# psu_temp.net
KiCad netlist of a schematic drawn in Altium Designer
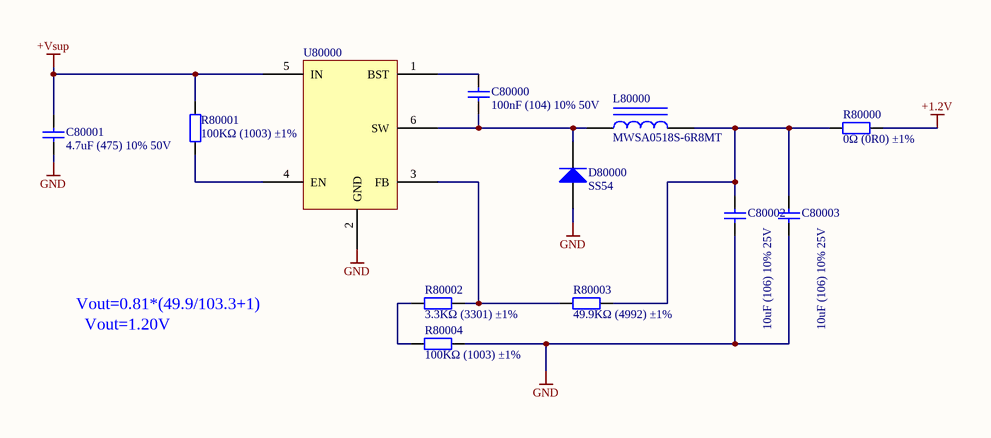
[diagram p0: psu_temp.SchDoc]

(export (version "E")
  (design (tool "Eeschema 10.0.6"))
  (components
    (comp (ref "C80000")
      (value "100nF (104) 10% 50V")
      (footprint "0603_C")
      (description "贴片电容")
      (libsource (lib "Cap") (part "0603 100nF (104) 10% 50V"))
    )
    (comp (ref "C80001")
      (value "4.7uF (475) 10% 50V")
      (footprint "1206_C")
      (description "贴片电容")
      (libsource (lib "Cap") (part "1206 4.7uF (475) 10% 50V"))
    )
    (comp (ref "C80002")
      (value "10uF (106) 10% 25V")
      (footprint "0805_C")
      (description "贴片电容")
      (libsource (lib "Cap") (part "0805 10uF (106) 10% 25V"))
    )
    (comp (ref "C80003")
      (value "10uF (106) 10% 25V")
      (footprint "0805_C")
      (description "贴片电容")
      (libsource (lib "Cap") (part "0805 10uF (106) 10% 25V"))
    )
    (comp (ref "D80000")
      (value "SS54")
      (footprint "SMA(DO-214AC)_S1")
      (description "二极管")
      (libsource (lib "Diode") (part "SMA(DO-214AC) SS54"))
    )
    (comp (ref "L80000")
      (value "MWSA0518S-6R8MT")
      (footprint "MWSA0518")
      (description "POWER INDUCTORS SMD,5.2X5.4X1.8MM ROHS")
      (libsource (lib "FPGA_PMU_lib") (part "MWSA0518S-6R8MT"))
    )
    (comp (ref "R80000")
      (value "0Ω (0R0) ±1%")
      (footprint "0805_R")
      (description "贴片电阻")
      (libsource (lib "RES") (part "0805 0Ω (0R0) 1%"))
    )
    (comp (ref "R80001")
      (value "100KΩ (1003) ±1%")
      (footprint "0402_R")
      (description "贴片电阻")
      (libsource (lib "RES") (part "0402 100KΩ (1003) 1%"))
    )
    (comp (ref "R80002")
      (value "3.3KΩ (3301) ±1%")
      (footprint "0402_R")
      (description "贴片电阻")
      (libsource (lib "RES") (part "0402 3.3KΩ (3301) 1%"))
    )
    (comp (ref "R80003")
      (value "49.9KΩ (4992) ±1%")
      (footprint "0402_R")
      (description "贴片电阻")
      (libsource (lib "RES") (part "0402 49.9KΩ (4992) 1%"))
    )
    (comp (ref "R80004")
      (value "100KΩ (1003) ±1%")
      (footprint "0402_R")
      (description "贴片电阻")
      (libsource (lib "") (part "0402 100KΩ (1003) 1%_1"))
    )
    (comp (ref "U80000")
      (value "STEP-DOWN CONVERTER")
      (footprint "*TSOT-23_S6")
      (description "1.2A, 24V, 1.4MHz STEP-DOWN CONVERTER IN A TSOT23-6")
      (libsource (lib "FPGA_PMU_lib") (part "MP2359"))
    )
  )
  (nets
    (net (code "1") (name "+1.2V") (class "Default")
      (node (ref "R80000") (pin "2") (pinfunction "2_2") (pintype "passive"))
    )
    (net (code "2") (name "+Vsup") (class "Default")
      (node (ref "C80001") (pin "2") (pinfunction "2_2") (pintype "passive"))
      (node (ref "R80001") (pin "2") (pinfunction "2_2") (pintype "passive"))
      (node (ref "U80000") (pin "5") (pinfunction "IN_5") (pintype "passive"))
    )
    (net (code "3") (name "GND") (class "Default")
      (node (ref "C80001") (pin "1") (pinfunction "1_1") (pintype "passive"))
      (node (ref "C80002") (pin "1") (pinfunction "1_1") (pintype "passive"))
      (node (ref "C80003") (pin "1") (pinfunction "1_1") (pintype "passive"))
      (node (ref "D80000") (pin "1") (pinfunction "A_1") (pintype "passive"))
      (node (ref "R80004") (pin "1") (pinfunction "1_1") (pintype "passive"))
      (node (ref "U80000") (pin "2") (pinfunction "GND_2") (pintype "passive"))
    )
    (net (code "4") (name "Net-(C80002-Pad2)") (class "Default")
      (node (ref "C80002") (pin "2") (pinfunction "2_2") (pintype "passive"))
      (node (ref "C80003") (pin "2") (pinfunction "2_2") (pintype "passive"))
      (node (ref "L80000") (pin "2") (pinfunction "2_2") (pintype "power_in"))
      (node (ref "R80000") (pin "1") (pinfunction "1_1") (pintype "passive"))
      (node (ref "R80003") (pin "2") (pinfunction "2_2") (pintype "passive"))
    )
    (net (code "5") (name "Net-(D80000-K)") (class "Default")
      (node (ref "C80000") (pin "1") (pinfunction "1_1") (pintype "passive"))
      (node (ref "D80000") (pin "2") (pinfunction "K_2") (pintype "passive"))
      (node (ref "L80000") (pin "1") (pinfunction "1_1") (pintype "power_in"))
      (node (ref "U80000") (pin "6") (pinfunction "SW_6") (pintype "passive"))
    )
    (net (code "6") (name "Net-(R80002-Pad2)") (class "Default")
      (node (ref "R80002") (pin "2") (pinfunction "2_2") (pintype "passive"))
      (node (ref "R80004") (pin "2") (pinfunction "2_2") (pintype "passive"))
    )
    (net (code "7") (name "Net-(U80000-BST)") (class "Default")
      (node (ref "C80000") (pin "2") (pinfunction "2_2") (pintype "passive"))
      (node (ref "U80000") (pin "1") (pinfunction "BST_1") (pintype "passive"))
    )
    (net (code "8") (name "Net-(U80000-EN)") (class "Default")
      (node (ref "R80001") (pin "1") (pinfunction "1_1") (pintype "passive"))
      (node (ref "U80000") (pin "4") (pinfunction "EN_4") (pintype "passive"))
    )
    (net (code "9") (name "Net-(U80000-FB)") (class "Default")
      (node (ref "R80002") (pin "1") (pinfunction "1_1") (pintype "passive"))
      (node (ref "R80003") (pin "1") (pinfunction "1_1") (pintype "passive"))
      (node (ref "U80000") (pin "3") (pinfunction "FB_3") (pintype "passive"))
    )
  )
)
